# motor.net
KiCad netlist of a schematic drawn in Altium Designer
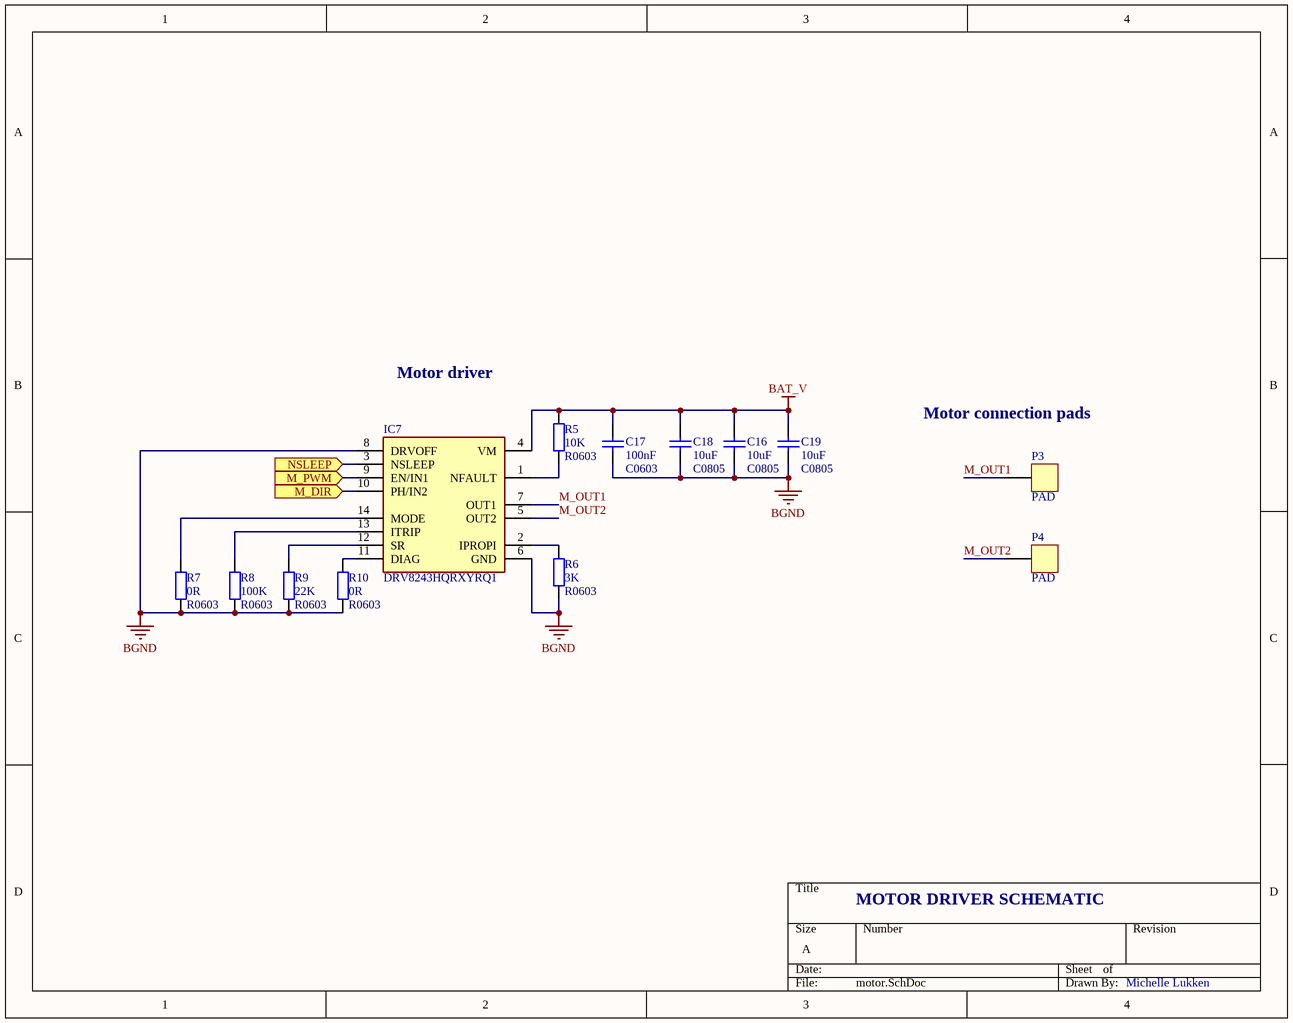
[diagram p0: motor.SchDoc]

(export (version "E")
  (design (tool "Eeschema 10.0.6"))
  (components
    (comp (ref "C16")
      (value "10uF*V")
      (footprint "C0805")
      (description "Ceramic capacitor")
      (fields (field (name "CAPACITANCE") "10uF"))
      (libsource (lib "Component Library INTLIB") (part "Capacitor"))
    )
    (comp (ref "C17")
      (value "100nF*V")
      (footprint "PCB Passives:C0603")
      (description "Ceramic capacitor")
      (fields (field (name "CAPACITANCE") "100nF"))
      (libsource (lib "DeltaX_basketball_mikro") (part "Capacitor"))
    )
    (comp (ref "C18")
      (value "10uF*V")
      (footprint "C0805")
      (description "Ceramic capacitor")
      (fields (field (name "CAPACITANCE") "10uF"))
      (libsource (lib "Component Library INTLIB") (part "Capacitor"))
    )
    (comp (ref "C19")
      (value "10uF*V")
      (footprint "C0805")
      (description "Ceramic capacitor")
      (fields (field (name "CAPACITANCE") "10uF"))
      (libsource (lib "Component Library INTLIB") (part "Capacitor"))
    )
    (comp (ref "IC7")
      (value "DRV8243HQRXYRQ1")
      (footprint "SamacSys:DRV8243HQRXYRQ1")
      (description "Integrated Circuit")
      (libsource (lib "DeltaX_basketball_mikro") (part "DRV8243HQRXYRQ1"))
    )
    (comp (ref "P3") (value "PAD") (footprint "PAD") (libsource (lib "SamacSys") (part "PAD")))
    (comp (ref "P4") (value "PAD") (footprint "PAD") (libsource (lib "SamacSys") (part "PAD")))
    (comp (ref "R5")
      (value "10K")
      (footprint "R0603")
      (description "Resistor")
      (fields (field (name "RESISTANCE") "10K"))
      (libsource (lib "Component Library INTLIB") (part "Resistor"))
    )
    (comp (ref "R6")
      (value "3K")
      (footprint "R0603")
      (description "Resistor")
      (fields (field (name "RESISTANCE") "3K"))
      (libsource (lib "Component Library INTLIB") (part "Resistor"))
    )
    (comp (ref "R7")
      (value "0R")
      (footprint "R0603")
      (description "Resistor")
      (fields (field (name "RESISTANCE") "0R"))
      (libsource (lib "Component Library INTLIB") (part "Resistor"))
    )
    (comp (ref "R8")
      (value "100K")
      (footprint "R0603")
      (description "Resistor")
      (fields (field (name "RESISTANCE") "100K"))
      (libsource (lib "Component Library INTLIB") (part "Resistor"))
    )
    (comp (ref "R9")
      (value "22K")
      (footprint "R0603")
      (description "Resistor")
      (fields (field (name "RESISTANCE") "22K"))
      (libsource (lib "Component Library INTLIB") (part "Resistor"))
    )
    (comp (ref "R10")
      (value "0R")
      (footprint "R0603")
      (description "Resistor")
      (fields (field (name "RESISTANCE") "0R"))
      (libsource (lib "Component Library INTLIB") (part "Resistor"))
    )
  )
  (nets
    (net (code "1") (name "/M_DIR") (class "Default")
      (node (ref "IC7") (pin "10") (pinfunction "PH/IN2_10") (pintype "passive"))
    )
    (net (code "2") (name "/M_OUT1") (class "Default")
      (node (ref "IC7") (pin "7") (pinfunction "OUT1_7") (pintype "passive"))
      (node (ref "P3") (pin "1") (pinfunction "PAD_1") (pintype "passive"))
    )
    (net (code "3") (name "/M_OUT2") (class "Default")
      (node (ref "IC7") (pin "5") (pinfunction "OUT2_5") (pintype "passive"))
      (node (ref "P4") (pin "1") (pinfunction "PAD_1") (pintype "passive"))
    )
    (net (code "4") (name "/M_PWM") (class "Default")
      (node (ref "IC7") (pin "9") (pinfunction "EN/IN1_9") (pintype "passive"))
    )
    (net (code "5") (name "/NSLEEP") (class "Default")
      (node (ref "IC7") (pin "3") (pinfunction "NSLEEP_3") (pintype "passive"))
    )
    (net (code "6") (name "BAT_V") (class "Default")
      (node (ref "C16") (pin "2") (pinfunction "2_2") (pintype "passive"))
      (node (ref "C17") (pin "2") (pinfunction "2_2") (pintype "passive"))
      (node (ref "C18") (pin "2") (pinfunction "2_2") (pintype "passive"))
      (node (ref "C19") (pin "2") (pinfunction "2_2") (pintype "passive"))
      (node (ref "IC7") (pin "4") (pinfunction "VM_4") (pintype "passive"))
      (node (ref "R5") (pin "2") (pinfunction "2_2") (pintype "passive"))
    )
    (net (code "7") (name "BGND") (class "Default")
      (node (ref "C16") (pin "1") (pinfunction "1_1") (pintype "passive"))
      (node (ref "C17") (pin "1") (pinfunction "1_1") (pintype "passive"))
      (node (ref "C18") (pin "1") (pinfunction "1_1") (pintype "passive"))
      (node (ref "C19") (pin "1") (pinfunction "1_1") (pintype "passive"))
      (node (ref "IC7") (pin "6") (pinfunction "GND_6") (pintype "passive"))
      (node (ref "IC7") (pin "8") (pinfunction "DRVOFF_8") (pintype "passive"))
      (node (ref "R10") (pin "1") (pinfunction "1_1") (pintype "passive"))
      (node (ref "R6") (pin "1") (pinfunction "1_1") (pintype "passive"))
      (node (ref "R7") (pin "1") (pinfunction "1_1") (pintype "passive"))
      (node (ref "R8") (pin "1") (pinfunction "1_1") (pintype "passive"))
      (node (ref "R9") (pin "1") (pinfunction "1_1") (pintype "passive"))
    )
    (net (code "8") (name "Net-(IC7-DIAG)") (class "Default")
      (node (ref "IC7") (pin "11") (pinfunction "DIAG_11") (pintype "passive"))
      (node (ref "R10") (pin "2") (pinfunction "2_2") (pintype "passive"))
    )
    (net (code "9") (name "Net-(IC7-IPROPI)") (class "Default")
      (node (ref "IC7") (pin "2") (pinfunction "IPROPI_2") (pintype "passive"))
      (node (ref "R6") (pin "2") (pinfunction "2_2") (pintype "passive"))
    )
    (net (code "10") (name "Net-(IC7-ITRIP)") (class "Default")
      (node (ref "IC7") (pin "13") (pinfunction "ITRIP_13") (pintype "passive"))
      (node (ref "R8") (pin "2") (pinfunction "2_2") (pintype "passive"))
    )
    (net (code "11") (name "Net-(IC7-MODE)") (class "Default")
      (node (ref "IC7") (pin "14") (pinfunction "MODE_14") (pintype "passive"))
      (node (ref "R7") (pin "2") (pinfunction "2_2") (pintype "passive"))
    )
    (net (code "12") (name "Net-(IC7-NFAULT)") (class "Default")
      (node (ref "IC7") (pin "1") (pinfunction "NFAULT_1") (pintype "passive"))
      (node (ref "R5") (pin "1") (pinfunction "1_1") (pintype "passive"))
    )
    (net (code "13") (name "Net-(IC7-SR)") (class "Default")
      (node (ref "IC7") (pin "12") (pinfunction "SR_12") (pintype "passive"))
      (node (ref "R9") (pin "2") (pinfunction "2_2") (pintype "passive"))
    )
  )
)
